# MI_LED_Driver_B.net
KiCad netlist of a schematic drawn in EAGLE
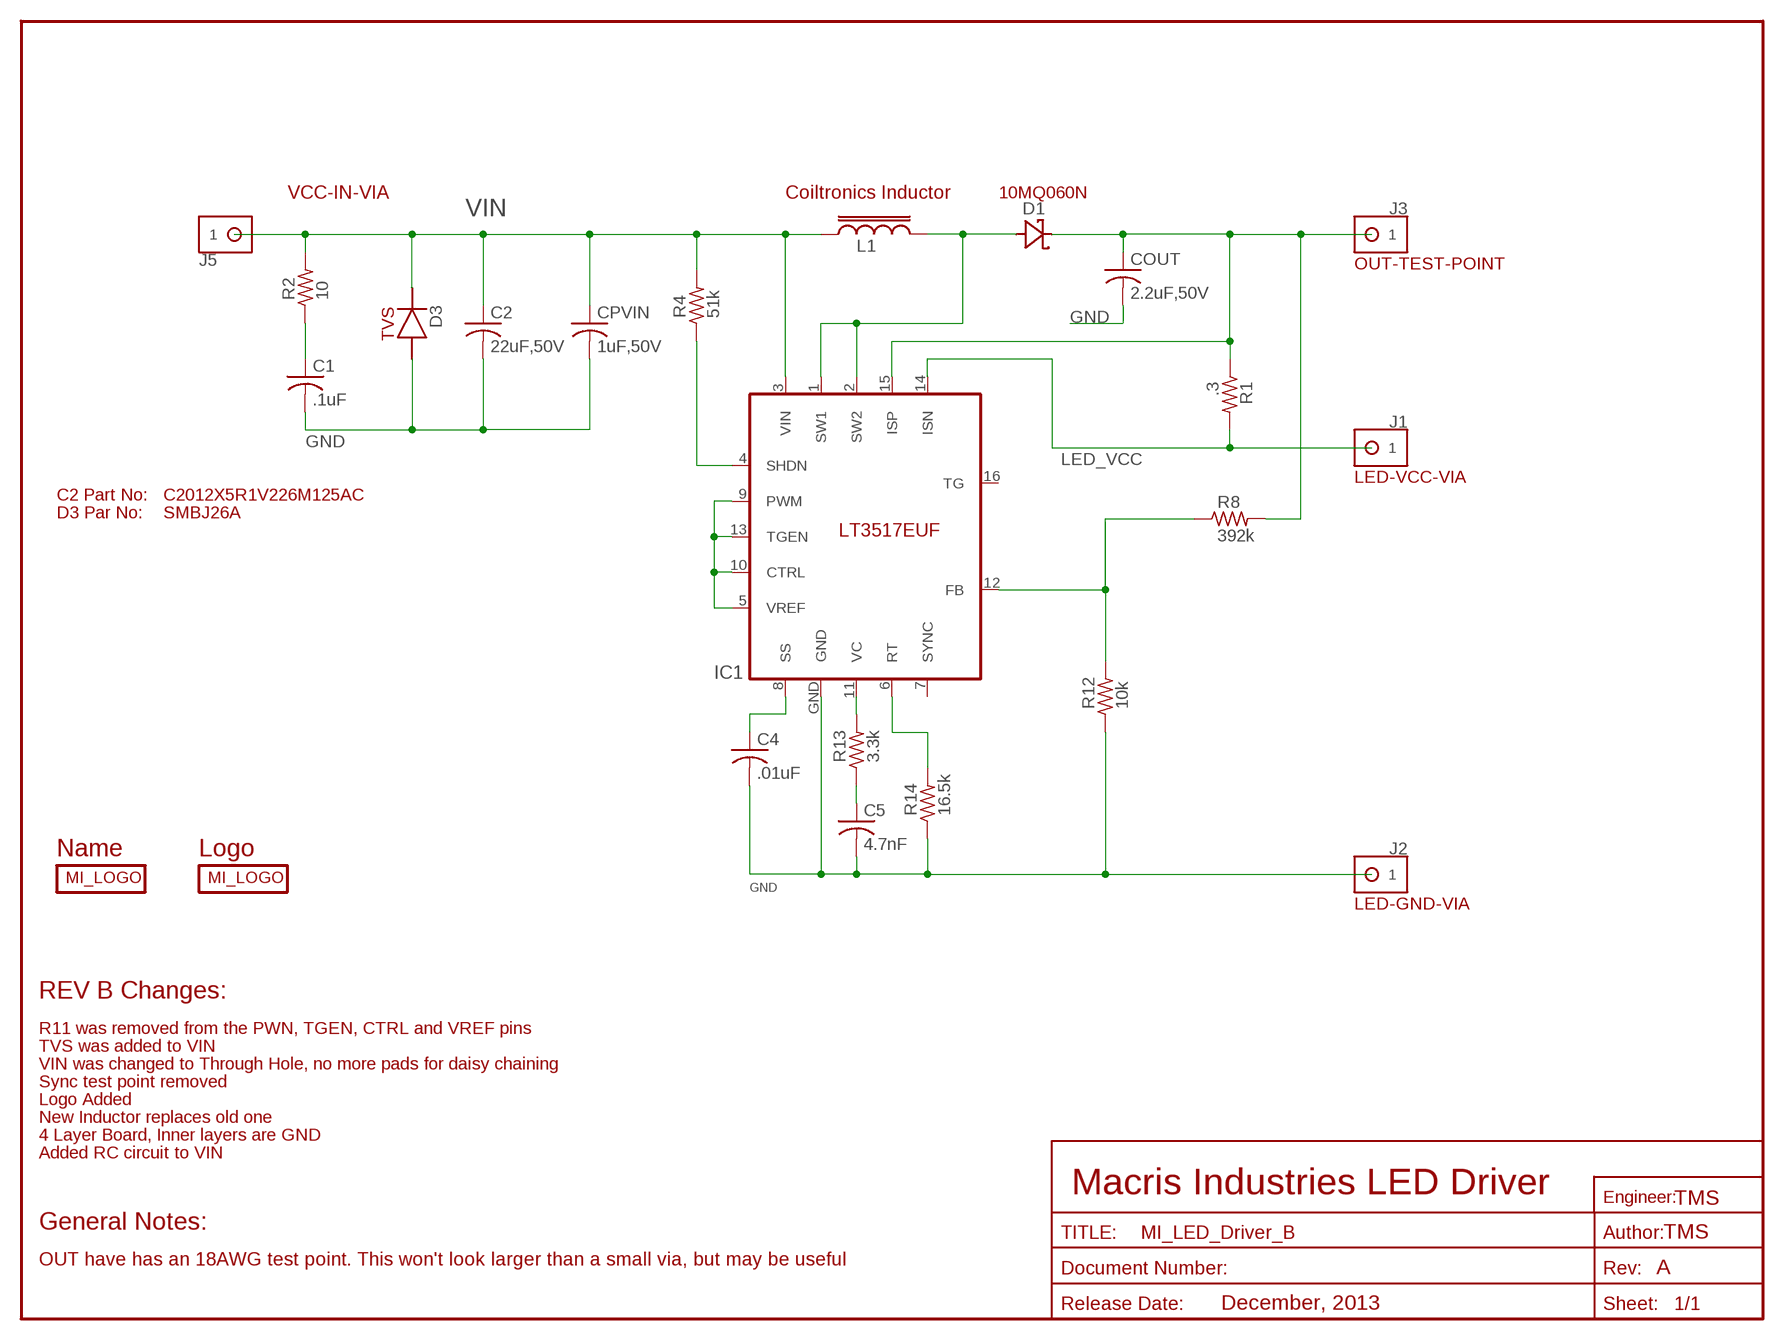
[diagram p0: schematic, sheet 1]

(export (version "E")
  (design (tool "Eeschema 10.0.6"))
  (components
    (comp (ref "C1")
      (value ".1uF")
      (footprint "eagle-import:C0805")
      (libsource (lib "eagle-import") (part "CAP-S0805"))
    )
    (comp (ref "C2")
      (value "22uF,50V")
      (footprint "eagle-import:C0805")
      (libsource (lib "eagle-import") (part "CAP-S0805"))
    )
    (comp (ref "C4")
      (value ".01uF")
      (footprint "eagle-import:C0805")
      (libsource (lib "eagle-import") (part "CAP-S0805"))
    )
    (comp (ref "C5")
      (value "4.7nF")
      (footprint "eagle-import:C0805")
      (libsource (lib "eagle-import") (part "CAP-S0805"))
    )
    (comp (ref "COUT")
      (value "2.2uF,50V")
      (footprint "eagle-import:C1206")
      (libsource (lib "eagle-import") (part "CAP-S1206"))
    )
    (comp (ref "CPVIN")
      (value "1uF,50V")
      (footprint "eagle-import:C1206")
      (libsource (lib "eagle-import") (part "CAP-S1206"))
    )
    (comp (ref "D1")
      (value "SCHOTTKY-DO-213AC-2")
      (footprint "eagle-import:DO-213AC-2")
      (libsource (lib "eagle-import") (part "SCHOTTKY-DO-213AC-2"))
    )
    (comp (ref "D3")
      (value "DIODE-DO-214AA")
      (footprint "eagle-import:DO-214AA")
      (libsource (lib "eagle-import") (part "DIODE-DO-214AA"))
    )
    (comp (ref "IC1")
      (value "LT3517")
      (footprint "eagle-import:QFN_SM")
      (libsource (lib "eagle-import") (part "LT3517"))
    )
    (comp (ref "J1")
      (value "HDR-1X1-14AWG")
      (footprint "eagle-import:14AWG-SOLDERPOINT")
      (libsource (lib "eagle-import") (part "HDR-1X1-14AWG"))
    )
    (comp (ref "J2")
      (value "HDR-1X1-14AWG")
      (footprint "eagle-import:14AWG-SOLDERPOINT")
      (libsource (lib "eagle-import") (part "HDR-1X1-14AWG"))
    )
    (comp (ref "J3")
      (value "HDR-1X1-18AWG_WIRE")
      (footprint "eagle-import:18AWG-SOLDERPOINT")
      (libsource (lib "eagle-import") (part "HDR-1X1-18AWG_WIRE"))
    )
    (comp (ref "J5")
      (value "HDR-1X1-14AWG")
      (footprint "eagle-import:14AWG-SOLDERPOINT")
      (libsource (lib "eagle-import") (part "HDR-1X1-14AWG"))
    )
    (comp (ref "L1")
      (value "IND-COILTRONICS-MPI4040")
      (footprint "eagle-import:IND-COILTRONICS")
      (libsource (lib "eagle-import") (part "IND-COILTRONICS-MPI4040"))
    )
    (comp (ref "R1")
      (value ".3")
      (footprint "eagle-import:R1206")
      (libsource (lib "eagle-import") (part "RES-S1206"))
    )
    (comp (ref "R2")
      (value "10")
      (footprint "eagle-import:R0805")
      (libsource (lib "eagle-import") (part "RES-S0805"))
    )
    (comp (ref "R4")
      (value "51k")
      (footprint "eagle-import:R0805")
      (libsource (lib "eagle-import") (part "RES-S0805"))
    )
    (comp (ref "R8")
      (value "392k")
      (footprint "eagle-import:R0805")
      (libsource (lib "eagle-import") (part "RES-S0805"))
    )
    (comp (ref "R12")
      (value "10k")
      (footprint "eagle-import:R0805")
      (libsource (lib "eagle-import") (part "RES-S0805"))
    )
    (comp (ref "R13")
      (value "3.3k")
      (footprint "eagle-import:R0805")
      (libsource (lib "eagle-import") (part "RES-S0805"))
    )
    (comp (ref "R14")
      (value "16.5k")
      (footprint "eagle-import:R0805")
      (libsource (lib "eagle-import") (part "RES-S0805"))
    )
    (comp (ref "U$1")
      (value "MI_LOGO-NAME_ONE")
      (footprint "eagle-import:MI_LOGO_NAME_1")
      (libsource (lib "eagle-import") (part "MI_LOGO-NAME_ONE"))
    )
    (comp (ref "U$2")
      (value "MI_LOGO-ONE")
      (footprint "eagle-import:MI_LOGO")
      (libsource (lib "eagle-import") (part "MI_LOGO-ONE"))
    )
  )
  (nets
    (net (code "1") (name "/GND") (class "Default")
      (node (ref "C1") (pin "2") (pinfunction "2_2") (pintype "passive"))
      (node (ref "C2") (pin "2") (pinfunction "2_2") (pintype "passive"))
      (node (ref "C4") (pin "2") (pinfunction "2_2") (pintype "passive"))
      (node (ref "C5") (pin "2") (pinfunction "2_2") (pintype "passive"))
      (node (ref "COUT") (pin "2") (pinfunction "2_2") (pintype "passive"))
      (node (ref "CPVIN") (pin "2") (pinfunction "2_2") (pintype "passive"))
      (node (ref "D3") (pin "ANODE") (pinfunction "A_ANODE") (pintype "bidirectional"))
      (node (ref "IC1") (pin "GND") (pinfunction "GND_GND") (pintype "bidirectional"))
      (node (ref "J2") (pin "P$1") (pinfunction "1_P$1") (pintype "passive"))
      (node (ref "R12") (pin "1") (pinfunction "1_1") (pintype "passive"))
      (node (ref "R14") (pin "1") (pinfunction "1_1") (pintype "passive"))
    )
    (net (code "2") (name "/LED_VCC") (class "Default")
      (node (ref "IC1") (pin "14") (pinfunction "ISN_14") (pintype "bidirectional"))
      (node (ref "J1") (pin "P$1") (pinfunction "1_P$1") (pintype "passive"))
      (node (ref "R1") (pin "2") (pinfunction "2_2") (pintype "passive"))
    )
    (net (code "3") (name "/VIN") (class "Default")
      (node (ref "C2") (pin "1") (pinfunction "1_1") (pintype "passive"))
      (node (ref "CPVIN") (pin "1") (pinfunction "1_1") (pintype "passive"))
      (node (ref "D3") (pin "CATH") (pinfunction "C_CATH") (pintype "bidirectional"))
      (node (ref "IC1") (pin "3") (pinfunction "VIN_3") (pintype "bidirectional"))
      (node (ref "J5") (pin "P$1") (pinfunction "1_P$1") (pintype "passive"))
      (node (ref "L1") (pin "DOT") (pinfunction "1_DOT") (pintype "bidirectional"))
      (node (ref "R2") (pin "2") (pinfunction "2_2") (pintype "passive"))
      (node (ref "R4") (pin "2") (pinfunction "2_2") (pintype "passive"))
    )
    (net (code "4") (name "Net-(C1-Pad1)") (class "Default")
      (node (ref "C1") (pin "1") (pinfunction "1_1") (pintype "passive"))
      (node (ref "R2") (pin "1") (pinfunction "1_1") (pintype "passive"))
    )
    (net (code "5") (name "Net-(C5-Pad1)") (class "Default")
      (node (ref "C5") (pin "1") (pinfunction "1_1") (pintype "passive"))
      (node (ref "R13") (pin "1") (pinfunction "1_1") (pintype "passive"))
    )
    (net (code "6") (name "Net-(IC1-CTRL)") (class "Default")
      (node (ref "IC1") (pin "10") (pinfunction "CTRL_10") (pintype "bidirectional"))
      (node (ref "IC1") (pin "13") (pinfunction "TGEN_13") (pintype "bidirectional"))
      (node (ref "IC1") (pin "5") (pinfunction "VREF_5") (pintype "bidirectional"))
      (node (ref "IC1") (pin "9") (pinfunction "PWM_9") (pintype "bidirectional"))
    )
    (net (code "7") (name "Net-(IC1-FB)") (class "Default")
      (node (ref "IC1") (pin "12") (pinfunction "FB_12") (pintype "bidirectional"))
      (node (ref "R12") (pin "2") (pinfunction "2_2") (pintype "passive"))
      (node (ref "R8") (pin "1") (pinfunction "1_1") (pintype "passive"))
    )
    (net (code "8") (name "Net-(IC1-ISP)") (class "Default")
      (node (ref "COUT") (pin "1") (pinfunction "1_1") (pintype "passive"))
      (node (ref "D1") (pin "C") (pinfunction "C_C") (pintype "bidirectional"))
      (node (ref "IC1") (pin "15") (pinfunction "ISP_15") (pintype "bidirectional"))
      (node (ref "J3") (pin "1") (pinfunction "1_1") (pintype "passive"))
      (node (ref "R1") (pin "1") (pinfunction "1_1") (pintype "passive"))
      (node (ref "R8") (pin "2") (pinfunction "2_2") (pintype "passive"))
    )
    (net (code "9") (name "Net-(IC1-RT)") (class "Default")
      (node (ref "IC1") (pin "6") (pinfunction "RT_6") (pintype "bidirectional"))
      (node (ref "R14") (pin "2") (pinfunction "2_2") (pintype "passive"))
    )
    (net (code "10") (name "Net-(IC1-SHDN)") (class "Default")
      (node (ref "IC1") (pin "4") (pinfunction "SHDN_4") (pintype "bidirectional"))
      (node (ref "R4") (pin "1") (pinfunction "1_1") (pintype "passive"))
    )
    (net (code "11") (name "Net-(IC1-SS)") (class "Default")
      (node (ref "C4") (pin "1") (pinfunction "1_1") (pintype "passive"))
      (node (ref "IC1") (pin "8") (pinfunction "SS_8") (pintype "bidirectional"))
    )
    (net (code "12") (name "Net-(IC1-SW1)") (class "Default")
      (node (ref "D1") (pin "A") (pinfunction "A_A") (pintype "bidirectional"))
      (node (ref "IC1") (pin "1") (pinfunction "SW1_1") (pintype "bidirectional"))
      (node (ref "IC1") (pin "2") (pinfunction "SW2_2") (pintype "bidirectional"))
      (node (ref "L1") (pin "NO_DOT") (pinfunction "2_NO_DOT") (pintype "bidirectional"))
    )
    (net (code "13") (name "Net-(IC1-VC)") (class "Default")
      (node (ref "IC1") (pin "11") (pinfunction "VC_11") (pintype "bidirectional"))
      (node (ref "R13") (pin "2") (pinfunction "2_2") (pintype "passive"))
    )
    (net (code "14") (name "unconnected-(IC1-SYNC-Pad7)") (class "Default")
      (node (ref "IC1") (pin "7") (pinfunction "SYNC_7") (pintype "bidirectional"))
    )
    (net (code "15") (name "unconnected-(IC1-TG-Pad16)") (class "Default")
      (node (ref "IC1") (pin "16") (pinfunction "TG_16") (pintype "bidirectional"))
    )
  )
)
